# top.net
KiCad netlist of a schematic drawn in Altium Designer
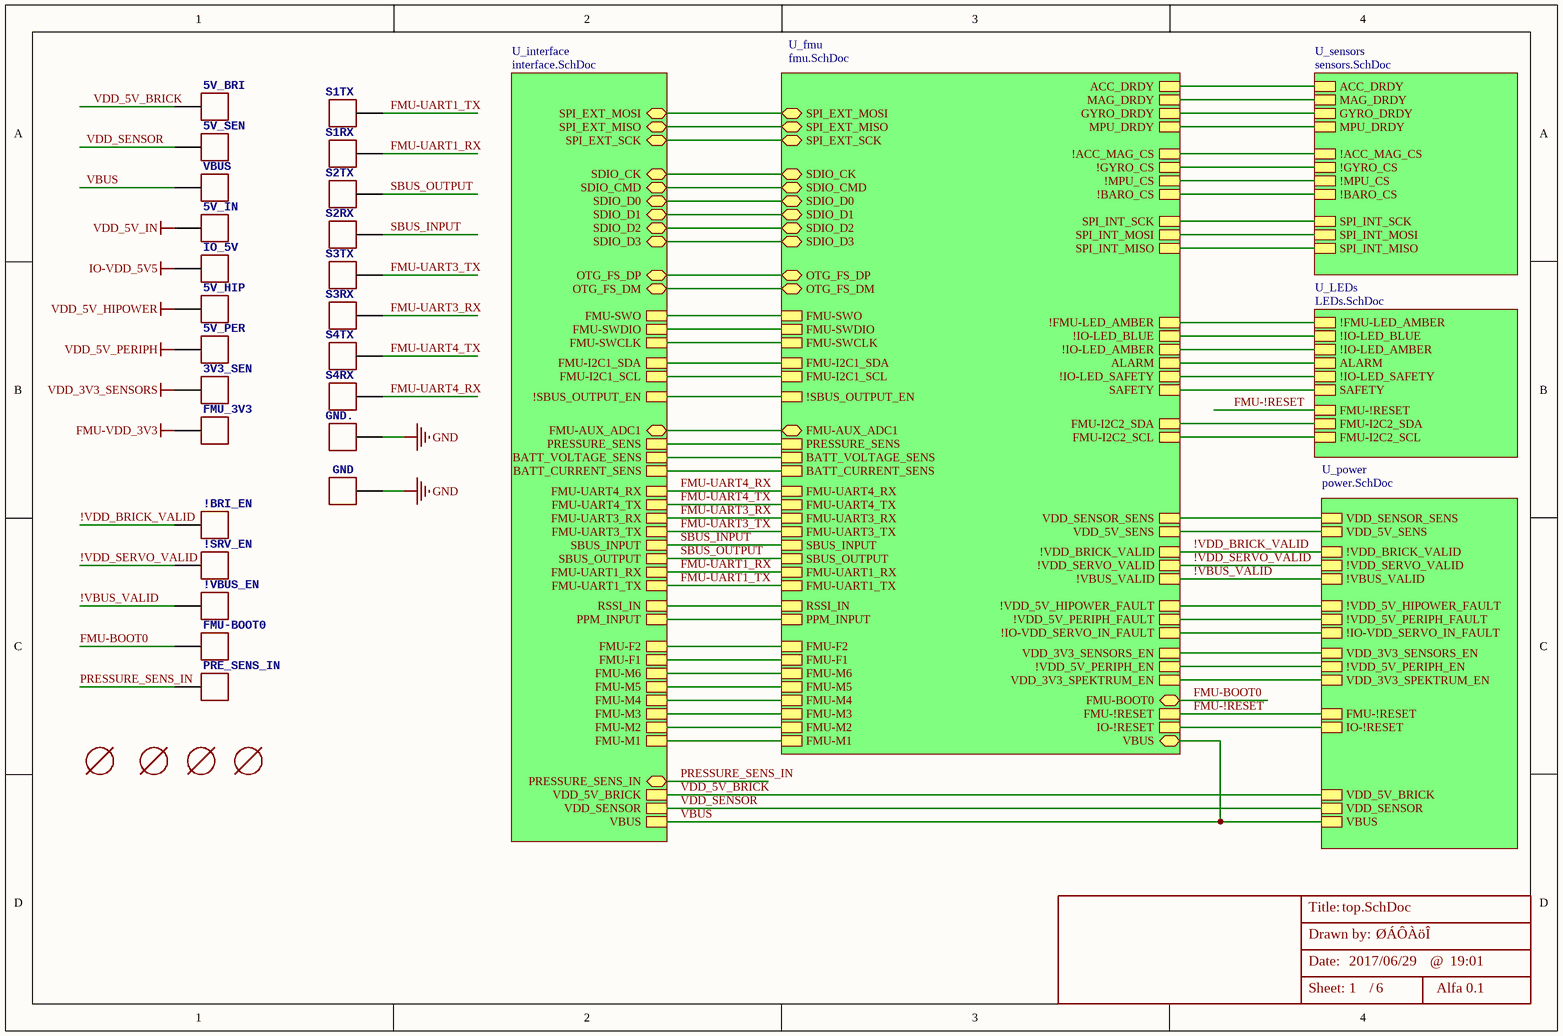
[diagram p0: top.SchDoc]

(export (version "E")
  (design (tool "Eeschema 10.0.6"))
  (components
    (comp (ref "!BRI_EN")
      (value "PAD.04")
      (footprint "PAD.04X.04")
      (description "!VDD_BRICK_VALID")
      (libsource (lib "FMU3_REV_D") (part "PAD.04"))
    )
    (comp (ref "!SRV_EN")
      (value "PAD.04")
      (footprint "PAD.04X.04")
      (description "!VDD_SERVO_VALID")
      (libsource (lib "FMU3_REV_D") (part "PAD.04"))
    )
    (comp (ref "!VBUS_EN")
      (value "PAD.04")
      (footprint "PAD.04X.04")
      (description "!VBUS_VALID")
      (libsource (lib "FMU3_REV_D") (part "PAD.04"))
    )
    (comp (ref "3V3_SEN")
      (value "PAD.04")
      (footprint "PAD.04X.04")
      (description "VDD_3V3_SENSORS")
      (libsource (lib "FMU3_REV_D") (part "PAD.04"))
    )
    (comp (ref "5V_BRI")
      (value "PAD.04")
      (footprint "PAD.04X.04")
      (description "VDD_5V_BRICK")
      (libsource (lib "FMU3_REV_D") (part "PAD.04"))
    )
    (comp (ref "5V_HIP")
      (value "PAD.04")
      (footprint "PAD.04X.04")
      (description "VDD_5V_HIPOWER")
      (libsource (lib "FMU3_REV_D") (part "PAD.04"))
    )
    (comp (ref "5V_IN")
      (value "PAD.04")
      (footprint "PAD.04X.04")
      (description "VDD_5V_IN")
      (libsource (lib "FMU3_REV_D") (part "PAD.04"))
    )
    (comp (ref "5V_PER")
      (value "PAD.04")
      (footprint "PAD.04X.04")
      (description "VDD_5V_PERIPH")
      (libsource (lib "FMU3_REV_D") (part "PAD.04"))
    )
    (comp (ref "5V_SEN")
      (value "PAD.04")
      (footprint "PAD.04X.04")
      (description "VDD_SENSOR")
      (libsource (lib "FMU3_REV_D") (part "PAD.04"))
    )
    (comp (ref "FMU-BOOT0")
      (value "PAD.04")
      (footprint "PAD.04X.04")
      (libsource (lib "FMU3_REV_D") (part "PAD.04"))
    )
    (comp (ref "FMU_3V3")
      (value "PAD.04")
      (footprint "PAD.04X.04")
      (description "FMU-VDD_3V3")
      (libsource (lib "FMU3_REV_D") (part "PAD.04"))
    )
    (comp (ref "GND")
      (value "PAD.04")
      (footprint "PAD.04X.04")
      (libsource (lib "FMU3_REV_D") (part "PAD.04"))
    )
    (comp (ref "GND.")
      (value "PAD.04")
      (footprint "PAD.04X.04")
      (libsource (lib "FMU3_REV_D") (part "PAD.04"))
    )
    (comp (ref "IO_5V")
      (value "PAD.04")
      (footprint "PAD.04X.04")
      (description "IO-VDD_5V5")
      (libsource (lib "FMU3_REV_D") (part "PAD.04"))
    )
    (comp (ref "M100")
      (value "MOUNT-HOLE1.8MM")
      (footprint "HOLE-3mm")
      (libsource (lib "FMU3_REV_D") (part "MOUNT-HOLE1.8MM"))
    )
    (comp (ref "M101")
      (value "MOUNT-HOLE1.8MM")
      (footprint "HOLE-3mm")
      (libsource (lib "FMU3_REV_D") (part "MOUNT-HOLE1.8MM"))
    )
    (comp (ref "M102")
      (value "MOUNT-HOLE1.8MM")
      (footprint "HOLE-3mm")
      (libsource (lib "FMU3_REV_D") (part "MOUNT-HOLE1.8MM"))
    )
    (comp (ref "M103")
      (value "MOUNT-HOLE1.8MM")
      (footprint "HOLE-3mm")
      (libsource (lib "FMU3_REV_D") (part "MOUNT-HOLE1.8MM"))
    )
    (comp (ref "PRE_SENS_IN")
      (value "PAD.04")
      (footprint "PAD.04X.04")
      (description "PRESSURE_SENS_IN")
      (libsource (lib "FMU3_REV_D") (part "PAD.04"))
    )
    (comp (ref "S1RX")
      (value "PAD.04")
      (footprint "PAD.04X.04")
      (libsource (lib "FMU3_REV_D") (part "PAD.04"))
    )
    (comp (ref "S1TX")
      (value "PAD.04")
      (footprint "PAD.04X.04")
      (libsource (lib "FMU3_REV_D") (part "PAD.04"))
    )
    (comp (ref "S2RX")
      (value "PAD.04")
      (footprint "PAD.04X.04")
      (libsource (lib "FMU3_REV_D") (part "PAD.04"))
    )
    (comp (ref "S2TX")
      (value "PAD.04")
      (footprint "PAD.04X.04")
      (libsource (lib "FMU3_REV_D") (part "PAD.04"))
    )
    (comp (ref "S3RX")
      (value "PAD.04")
      (footprint "PAD.04X.04")
      (libsource (lib "FMU3_REV_D") (part "PAD.04"))
    )
    (comp (ref "S3TX")
      (value "PAD.04")
      (footprint "PAD.04X.04")
      (libsource (lib "FMU3_REV_D") (part "PAD.04"))
    )
    (comp (ref "S4RX")
      (value "PAD.04")
      (footprint "PAD.04X.04")
      (libsource (lib "FMU3_REV_D") (part "PAD.04"))
    )
    (comp (ref "S4TX")
      (value "PAD.04")
      (footprint "PAD.04X.04")
      (libsource (lib "FMU3_REV_D") (part "PAD.04"))
    )
    (comp (ref "VBUS")
      (value "PAD.04")
      (footprint "PAD.04X.04")
      (libsource (lib "FMU3_REV_D") (part "PAD.04"))
    )
  )
  (nets
    (net (code "11") (name "/!VBUS_VALID") (class "Default")
      (node (ref "!VBUS_EN") (pin "P$1") (pinfunction "P$1_P$1") (pintype "passive"))
    )
    (net (code "15") (name "/!VDD_BRICK_VALID") (class "Default")
      (node (ref "!BRI_EN") (pin "P$1") (pinfunction "P$1_P$1") (pintype "passive"))
    )
    (net (code "16") (name "/!VDD_SERVO_VALID") (class "Default")
      (node (ref "!SRV_EN") (pin "P$1") (pinfunction "P$1_P$1") (pintype "passive"))
    )
    (net (code "23") (name "/FMU-BOOT0") (class "Default")
      (node (ref "FMU-BOOT0") (pin "P$1") (pinfunction "P$1_P$1") (pintype "passive"))
    )
    (net (code "39") (name "/FMU-UART1_RX") (class "Default")
      (node (ref "S1RX") (pin "P$1") (pinfunction "P$1_P$1") (pintype "passive"))
    )
    (net (code "40") (name "/FMU-UART1_TX") (class "Default")
      (node (ref "S1TX") (pin "P$1") (pinfunction "P$1_P$1") (pintype "passive"))
    )
    (net (code "41") (name "/FMU-UART3_RX") (class "Default")
      (node (ref "S3RX") (pin "P$1") (pinfunction "P$1_P$1") (pintype "passive"))
    )
    (net (code "42") (name "/FMU-UART3_TX") (class "Default")
      (node (ref "S3TX") (pin "P$1") (pinfunction "P$1_P$1") (pintype "passive"))
    )
    (net (code "43") (name "/FMU-UART4_RX") (class "Default")
      (node (ref "S4RX") (pin "P$1") (pinfunction "P$1_P$1") (pintype "passive"))
    )
    (net (code "44") (name "/FMU-UART4_TX") (class "Default")
      (node (ref "S4TX") (pin "P$1") (pinfunction "P$1_P$1") (pintype "passive"))
    )
    (net (code "53") (name "/PRESSURE_SENS_IN") (class "Default")
      (node (ref "PRE_SENS_IN") (pin "P$1") (pinfunction "P$1_P$1") (pintype "passive"))
    )
    (net (code "56") (name "/SBUS_INPUT") (class "Default")
      (node (ref "S2RX") (pin "P$1") (pinfunction "P$1_P$1") (pintype "passive"))
    )
    (net (code "57") (name "/SBUS_OUTPUT") (class "Default")
      (node (ref "S2TX") (pin "P$1") (pinfunction "P$1_P$1") (pintype "passive"))
    )
    (net (code "70") (name "/VBUS") (class "Default")
      (node (ref "VBUS") (pin "P$1") (pinfunction "P$1_P$1") (pintype "passive"))
    )
    (net (code "73") (name "/VDD_5V_BRICK") (class "Default")
      (node (ref "5V_BRI") (pin "P$1") (pinfunction "P$1_P$1") (pintype "passive"))
    )
    (net (code "75") (name "/VDD_SENSOR") (class "Default")
      (node (ref "5V_SEN") (pin "P$1") (pinfunction "P$1_P$1") (pintype "passive"))
    )
    (net (code "77") (name "FMU-VDD_3V3") (class "Default")
      (node (ref "FMU_3V3") (pin "P$1") (pinfunction "P$1_P$1") (pintype "passive"))
    )
    (net (code "78") (name "GND") (class "Default")
      (node (ref "GND") (pin "P$1") (pinfunction "P$1_P$1") (pintype "passive"))
      (node (ref "GND.") (pin "P$1") (pinfunction "P$1_P$1") (pintype "passive"))
    )
    (net (code "79") (name "IO-VDD_5V5") (class "Default")
      (node (ref "IO_5V") (pin "P$1") (pinfunction "P$1_P$1") (pintype "passive"))
    )
    (net (code "80") (name "VDD_3V3_SENSORS") (class "Default")
      (node (ref "3V3_SEN") (pin "P$1") (pinfunction "P$1_P$1") (pintype "passive"))
    )
    (net (code "81") (name "VDD_5V_HIPOWER") (class "Default")
      (node (ref "5V_HIP") (pin "P$1") (pinfunction "P$1_P$1") (pintype "passive"))
    )
    (net (code "82") (name "VDD_5V_IN") (class "Default")
      (node (ref "5V_IN") (pin "P$1") (pinfunction "P$1_P$1") (pintype "passive"))
    )
    (net (code "83") (name "VDD_5V_PERIPH") (class "Default")
      (node (ref "5V_PER") (pin "P$1") (pinfunction "P$1_P$1") (pintype "passive"))
    )
  )
)
